# SSOP-TSSOP20.net
KiCad netlist of a schematic drawn in Altium Designer
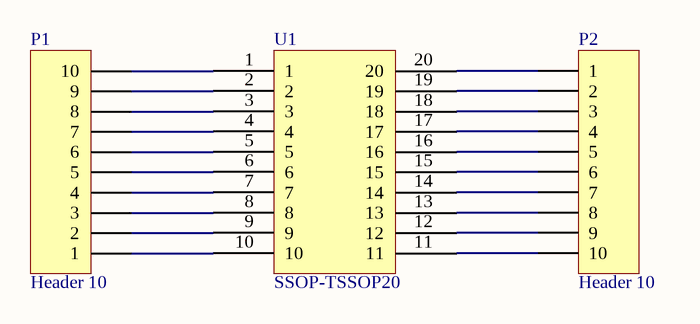
[diagram p0: SSOP-TSSOP20.SchDoc]

(export (version "E")
  (design (tool "Eeschema 10.0.6"))
  (components
    (comp (ref "P1")
      (value "Header 10")
      (footprint "HDR1X10")
      (description "Header, 10-Pin")
      (fields (field (name "PUBLISHER") "Altium Limited"))
      (libsource (lib "") (part "Header 10_1"))
    )
    (comp (ref "P2")
      (value "Header 10")
      (footprint "HDR1X10")
      (description "Header, 10-Pin")
      (fields (field (name "PUBLISHER") "Altium Limited"))
      (libsource (lib "Miscellaneous Connectors") (part "Header 10"))
    )
    (comp (ref "U1")
      (value "SSOP-TSSOP20")
      (footprint "SSOP-TSSOP20")
      (libsource (lib "PCB_Breakout_Boards") (part "SSOP-TSSOP20"))
    )
  )
  (nets
    (net (code "1") (name "Net-(P1-Pad1)") (class "Default")
      (node (ref "P1") (pin "1") (pinfunction "1_1") (pintype "passive"))
      (node (ref "U1") (pin "10") (pinfunction "10_10") (pintype "passive"))
    )
    (net (code "2") (name "Net-(P1-Pad2)") (class "Default")
      (node (ref "P1") (pin "2") (pinfunction "2_2") (pintype "passive"))
      (node (ref "U1") (pin "9") (pinfunction "9_9") (pintype "passive"))
    )
    (net (code "3") (name "Net-(P1-Pad3)") (class "Default")
      (node (ref "P1") (pin "3") (pinfunction "3_3") (pintype "passive"))
      (node (ref "U1") (pin "8") (pinfunction "8_8") (pintype "passive"))
    )
    (net (code "4") (name "Net-(P1-Pad4)") (class "Default")
      (node (ref "P1") (pin "4") (pinfunction "4_4") (pintype "passive"))
      (node (ref "U1") (pin "7") (pinfunction "7_7") (pintype "passive"))
    )
    (net (code "5") (name "Net-(P1-Pad5)") (class "Default")
      (node (ref "P1") (pin "5") (pinfunction "5_5") (pintype "passive"))
      (node (ref "U1") (pin "6") (pinfunction "6_6") (pintype "passive"))
    )
    (net (code "6") (name "Net-(P1-Pad6)") (class "Default")
      (node (ref "P1") (pin "6") (pinfunction "6_6") (pintype "passive"))
      (node (ref "U1") (pin "5") (pinfunction "5_5") (pintype "passive"))
    )
    (net (code "7") (name "Net-(P1-Pad7)") (class "Default")
      (node (ref "P1") (pin "7") (pinfunction "7_7") (pintype "passive"))
      (node (ref "U1") (pin "4") (pinfunction "4_4") (pintype "passive"))
    )
    (net (code "8") (name "Net-(P1-Pad8)") (class "Default")
      (node (ref "P1") (pin "8") (pinfunction "8_8") (pintype "passive"))
      (node (ref "U1") (pin "3") (pinfunction "3_3") (pintype "passive"))
    )
    (net (code "9") (name "Net-(P1-Pad9)") (class "Default")
      (node (ref "P1") (pin "9") (pinfunction "9_9") (pintype "passive"))
      (node (ref "U1") (pin "2") (pinfunction "2_2") (pintype "passive"))
    )
    (net (code "10") (name "Net-(P1-Pad10)") (class "Default")
      (node (ref "P1") (pin "10") (pinfunction "10_10") (pintype "passive"))
      (node (ref "U1") (pin "1") (pinfunction "1_1") (pintype "passive"))
    )
    (net (code "11") (name "Net-(P2-Pad1)") (class "Default")
      (node (ref "P2") (pin "1") (pinfunction "1_1") (pintype "passive"))
      (node (ref "U1") (pin "20") (pinfunction "20_20") (pintype "passive"))
    )
    (net (code "12") (name "Net-(P2-Pad2)") (class "Default")
      (node (ref "P2") (pin "2") (pinfunction "2_2") (pintype "passive"))
      (node (ref "U1") (pin "19") (pinfunction "19_19") (pintype "passive"))
    )
    (net (code "13") (name "Net-(P2-Pad3)") (class "Default")
      (node (ref "P2") (pin "3") (pinfunction "3_3") (pintype "passive"))
      (node (ref "U1") (pin "18") (pinfunction "18_18") (pintype "passive"))
    )
    (net (code "14") (name "Net-(P2-Pad4)") (class "Default")
      (node (ref "P2") (pin "4") (pinfunction "4_4") (pintype "passive"))
      (node (ref "U1") (pin "17") (pinfunction "17_17") (pintype "passive"))
    )
    (net (code "15") (name "Net-(P2-Pad5)") (class "Default")
      (node (ref "P2") (pin "5") (pinfunction "5_5") (pintype "passive"))
      (node (ref "U1") (pin "16") (pinfunction "16_16") (pintype "passive"))
    )
    (net (code "16") (name "Net-(P2-Pad6)") (class "Default")
      (node (ref "P2") (pin "6") (pinfunction "6_6") (pintype "passive"))
      (node (ref "U1") (pin "15") (pinfunction "15_15") (pintype "passive"))
    )
    (net (code "17") (name "Net-(P2-Pad7)") (class "Default")
      (node (ref "P2") (pin "7") (pinfunction "7_7") (pintype "passive"))
      (node (ref "U1") (pin "14") (pinfunction "14_14") (pintype "passive"))
    )
    (net (code "18") (name "Net-(P2-Pad8)") (class "Default")
      (node (ref "P2") (pin "8") (pinfunction "8_8") (pintype "passive"))
      (node (ref "U1") (pin "13") (pinfunction "13_13") (pintype "passive"))
    )
    (net (code "19") (name "Net-(P2-Pad9)") (class "Default")
      (node (ref "P2") (pin "9") (pinfunction "9_9") (pintype "passive"))
      (node (ref "U1") (pin "12") (pinfunction "12_12") (pintype "passive"))
    )
    (net (code "20") (name "Net-(P2-Pad10)") (class "Default")
      (node (ref "P2") (pin "10") (pinfunction "10_10") (pintype "passive"))
      (node (ref "U1") (pin "11") (pinfunction "11_11") (pintype "passive"))
    )
  )
)
